# MCU.net
KiCad netlist of a schematic drawn in Altium Designer
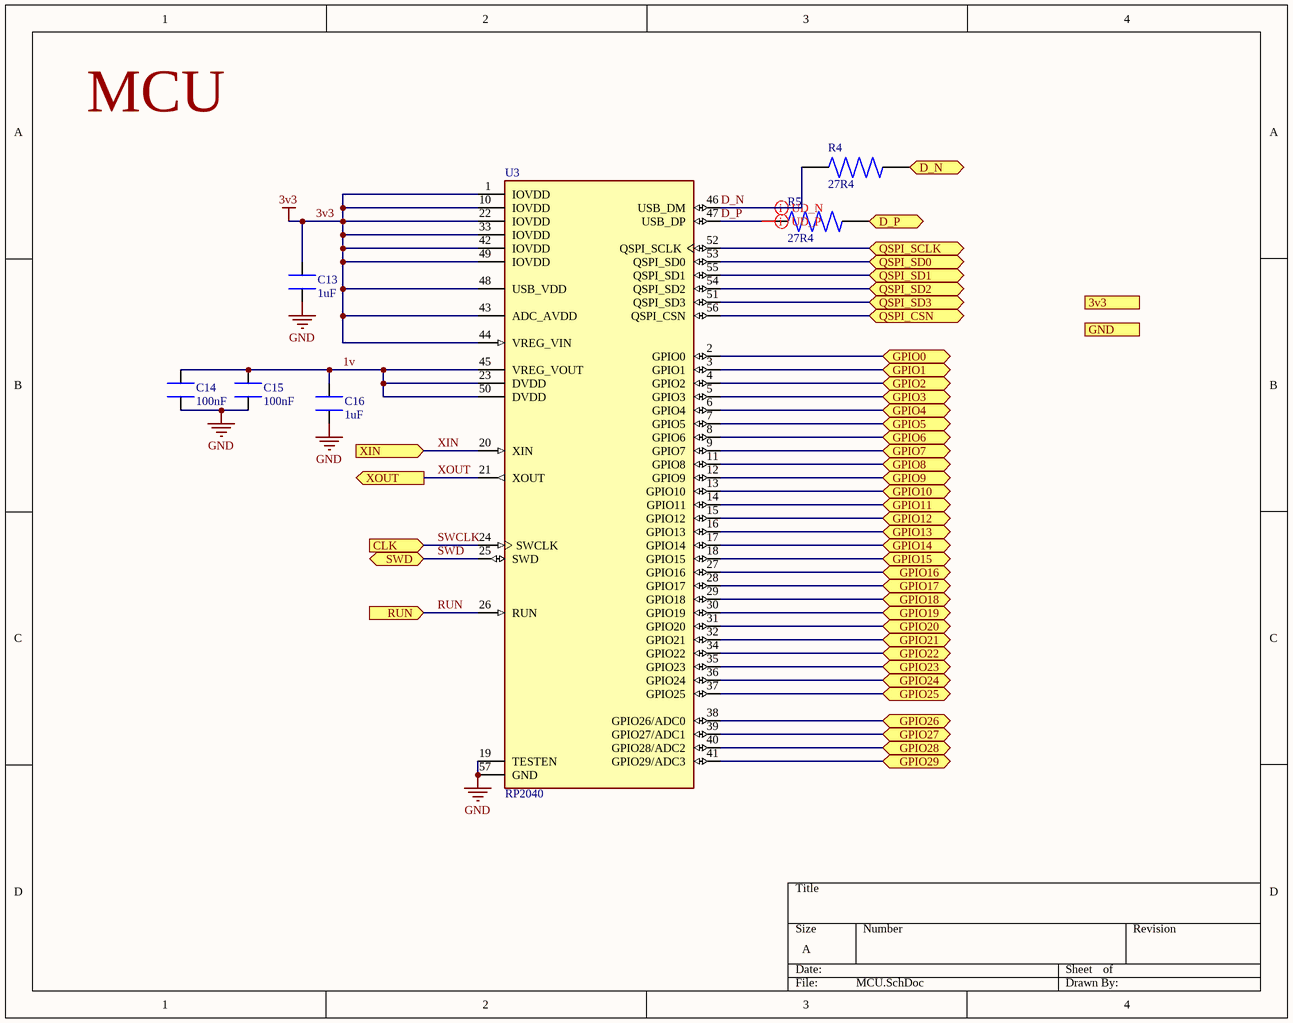
[diagram p0: MCU.SchDoc]

(export (version "E")
  (design (tool "Eeschema 10.0.6"))
  (components
    (comp (ref "C13")
      (value "1uF")
      (footprint "CC0603KRX5R8BB105")
      (description "SMD ceramic capasitor 1uF")
      (fields (field (name "MF") "Yageo") (field (name "MP") "CC0603KRX5R8BB105"))
      (libsource (lib "RP2040intLib") (part "CC0603KRX5R8BB105"))
    )
    (comp (ref "C14")
      (value "100nF")
      (footprint "CL10B104KB8NNNC")
      (description "SMD ceramic capacitor 0.1µF, tolerance ±10% 50V 0603 _1608 Metric_")
      (fields (field (name "MP") "CL10B104KB8NNNC") (field (name "MF") "Samsung Electro-Mechanics"))
      (libsource (lib "RP2040intLib") (part "CL10B104KB8NNNC"))
    )
    (comp (ref "C15")
      (value "100nF")
      (footprint "CL10B104KB8NNNC")
      (description "SMD ceramic capacitor 0.1µF, tolerance ±10% 50V 0603 _1608 Metric_")
      (fields (field (name "MP") "CL10B104KB8NNNC") (field (name "MF") "Samsung Electro-Mechanics"))
      (libsource (lib "RP2040intLib") (part "CL10B104KB8NNNC"))
    )
    (comp (ref "C16")
      (value "1uF")
      (footprint "CC0603KRX5R8BB105")
      (description "SMD ceramic capasitor 1uF")
      (fields (field (name "MF") "Yageo") (field (name "MP") "CC0603KRX5R8BB105"))
      (libsource (lib "RP2040intLib") (part "CC0603KRX5R8BB105"))
    )
    (comp (ref "R4")
      (value "27R4")
      (footprint "RC0603FR-0727R4L")
      (description "RES SMD 27.4 OHM 1% 1/10W 0603")
      (fields (field (name "MP") "RC0603FR-0727R4L"))
      (libsource (lib "RP2040intLib") (part "RC0603FR-0727R4L"))
    )
    (comp (ref "R5")
      (value "27R4")
      (footprint "RC0603FR-0727R4L")
      (description "RES SMD 27.4 OHM 1% 1/10W 0603")
      (fields (field (name "MP") "RC0603FR-0727R4L"))
      (libsource (lib "RP2040intLib") (part "RC0603FR-0727R4L"))
    )
    (comp (ref "U3")
      (value "RP2040")
      (footprint "RP2040")
      (description "RP2040 chip for Raspberry Pi Pico - ARM® Cortex®-M0+ MCU 32-Bit")
      (fields (field (name "MF") "Raspberry Pi"))
      (libsource (lib "RP2040intLib") (part "RP2040"))
    )
  )
  (nets
    (net (code "1") (name "/1v") (class "Default")
      (node (ref "C14") (pin "2") (pinfunction "2_2") (pintype "passive"))
      (node (ref "C15") (pin "2") (pinfunction "2_2") (pintype "passive"))
      (node (ref "C16") (pin "1") (pinfunction "1_1") (pintype "passive"))
      (node (ref "U3") (pin "23") (pinfunction "DVDD_23") (pintype "power_in"))
      (node (ref "U3") (pin "45") (pinfunction "VREG_VOUT_45") (pintype "power_in"))
      (node (ref "U3") (pin "50") (pinfunction "DVDD_50") (pintype "power_in"))
    )
    (net (code "2") (name "/D_N") (class "Default")
      (node (ref "R4") (pin "1") (pinfunction "1_1") (pintype "passive"))
      (node (ref "U3") (pin "46") (pinfunction "USB_DM_46") (pintype "bidirectional"))
    )
    (net (code "3") (name "/D_P") (class "Default")
      (node (ref "R5") (pin "1") (pinfunction "1_1") (pintype "passive"))
      (node (ref "U3") (pin "47") (pinfunction "USB_DP_47") (pintype "bidirectional"))
    )
    (net (code "4") (name "/GPIO0") (class "Default")
      (node (ref "U3") (pin "2") (pinfunction "GPIO0_2") (pintype "bidirectional"))
    )
    (net (code "5") (name "/GPIO1") (class "Default")
      (node (ref "U3") (pin "3") (pinfunction "GPIO1_3") (pintype "bidirectional"))
    )
    (net (code "6") (name "/GPIO2") (class "Default")
      (node (ref "U3") (pin "4") (pinfunction "GPIO2_4") (pintype "bidirectional"))
    )
    (net (code "7") (name "/GPIO3") (class "Default")
      (node (ref "U3") (pin "5") (pinfunction "GPIO3_5") (pintype "bidirectional"))
    )
    (net (code "8") (name "/GPIO4") (class "Default")
      (node (ref "U3") (pin "6") (pinfunction "GPIO4_6") (pintype "bidirectional"))
    )
    (net (code "9") (name "/GPIO5") (class "Default")
      (node (ref "U3") (pin "7") (pinfunction "GPIO5_7") (pintype "bidirectional"))
    )
    (net (code "10") (name "/GPIO6") (class "Default")
      (node (ref "U3") (pin "8") (pinfunction "GPIO6_8") (pintype "bidirectional"))
    )
    (net (code "11") (name "/GPIO7") (class "Default")
      (node (ref "U3") (pin "9") (pinfunction "GPIO7_9") (pintype "bidirectional"))
    )
    (net (code "12") (name "/GPIO8") (class "Default")
      (node (ref "U3") (pin "11") (pinfunction "GPIO8_11") (pintype "bidirectional"))
    )
    (net (code "13") (name "/GPIO9") (class "Default")
      (node (ref "U3") (pin "12") (pinfunction "GPIO9_12") (pintype "bidirectional"))
    )
    (net (code "14") (name "/GPIO10") (class "Default")
      (node (ref "U3") (pin "13") (pinfunction "GPIO10_13") (pintype "bidirectional"))
    )
    (net (code "15") (name "/GPIO11") (class "Default")
      (node (ref "U3") (pin "14") (pinfunction "GPIO11_14") (pintype "bidirectional"))
    )
    (net (code "16") (name "/GPIO12") (class "Default")
      (node (ref "U3") (pin "15") (pinfunction "GPIO12_15") (pintype "bidirectional"))
    )
    (net (code "17") (name "/GPIO13") (class "Default")
      (node (ref "U3") (pin "16") (pinfunction "GPIO13_16") (pintype "bidirectional"))
    )
    (net (code "18") (name "/GPIO14") (class "Default")
      (node (ref "U3") (pin "17") (pinfunction "GPIO14_17") (pintype "bidirectional"))
    )
    (net (code "19") (name "/GPIO15") (class "Default")
      (node (ref "U3") (pin "18") (pinfunction "GPIO15_18") (pintype "bidirectional"))
    )
    (net (code "20") (name "/GPIO16") (class "Default")
      (node (ref "U3") (pin "27") (pinfunction "GPIO16_27") (pintype "bidirectional"))
    )
    (net (code "21") (name "/GPIO17") (class "Default")
      (node (ref "U3") (pin "28") (pinfunction "GPIO17_28") (pintype "bidirectional"))
    )
    (net (code "22") (name "/GPIO18") (class "Default")
      (node (ref "U3") (pin "29") (pinfunction "GPIO18_29") (pintype "bidirectional"))
    )
    (net (code "23") (name "/GPIO19") (class "Default")
      (node (ref "U3") (pin "30") (pinfunction "GPIO19_30") (pintype "bidirectional"))
    )
    (net (code "24") (name "/GPIO20") (class "Default")
      (node (ref "U3") (pin "31") (pinfunction "GPIO20_31") (pintype "bidirectional"))
    )
    (net (code "25") (name "/GPIO21") (class "Default")
      (node (ref "U3") (pin "32") (pinfunction "GPIO21_32") (pintype "bidirectional"))
    )
    (net (code "26") (name "/GPIO22") (class "Default")
      (node (ref "U3") (pin "34") (pinfunction "GPIO22_34") (pintype "bidirectional"))
    )
    (net (code "27") (name "/GPIO23") (class "Default")
      (node (ref "U3") (pin "35") (pinfunction "GPIO23_35") (pintype "bidirectional"))
    )
    (net (code "28") (name "/GPIO24") (class "Default")
      (node (ref "U3") (pin "36") (pinfunction "GPIO24_36") (pintype "bidirectional"))
    )
    (net (code "29") (name "/GPIO25") (class "Default")
      (node (ref "U3") (pin "37") (pinfunction "GPIO25_37") (pintype "bidirectional"))
    )
    (net (code "30") (name "/GPIO26") (class "Default")
      (node (ref "U3") (pin "38") (pinfunction "GPIO26/ADC0_38") (pintype "bidirectional"))
    )
    (net (code "31") (name "/GPIO27") (class "Default")
      (node (ref "U3") (pin "39") (pinfunction "GPIO27/ADC1_39") (pintype "bidirectional"))
    )
    (net (code "32") (name "/GPIO28") (class "Default")
      (node (ref "U3") (pin "40") (pinfunction "GPIO28/ADC2_40") (pintype "bidirectional"))
    )
    (net (code "33") (name "/GPIO29") (class "Default")
      (node (ref "U3") (pin "41") (pinfunction "GPIO29/ADC3_41") (pintype "bidirectional"))
    )
    (net (code "34") (name "/QSPI_CSN") (class "Default")
      (node (ref "U3") (pin "56") (pinfunction "QSPI_CSN_56") (pintype "bidirectional"))
    )
    (net (code "35") (name "/QSPI_SCLK") (class "Default")
      (node (ref "U3") (pin "52") (pinfunction "QSPI_SCLK_52") (pintype "bidirectional"))
    )
    (net (code "36") (name "/QSPI_SD0") (class "Default")
      (node (ref "U3") (pin "53") (pinfunction "QSPI_SD0_53") (pintype "bidirectional"))
    )
    (net (code "37") (name "/QSPI_SD1") (class "Default")
      (node (ref "U3") (pin "55") (pinfunction "QSPI_SD1_55") (pintype "bidirectional"))
    )
    (net (code "38") (name "/QSPI_SD2") (class "Default")
      (node (ref "U3") (pin "54") (pinfunction "QSPI_SD2_54") (pintype "bidirectional"))
    )
    (net (code "39") (name "/QSPI_SD3") (class "Default")
      (node (ref "U3") (pin "51") (pinfunction "QSPI_SD3_51") (pintype "bidirectional"))
    )
    (net (code "40") (name "/RUN") (class "Default")
      (node (ref "U3") (pin "26") (pinfunction "RUN_26") (pintype "input"))
    )
    (net (code "41") (name "/SWCLK") (class "Default")
      (node (ref "U3") (pin "24") (pinfunction "SWCLK_24") (pintype "input"))
    )
    (net (code "42") (name "/SWD") (class "Default")
      (node (ref "U3") (pin "25") (pinfunction "SWD_25") (pintype "bidirectional"))
    )
    (net (code "43") (name "/XIN") (class "Default")
      (node (ref "U3") (pin "20") (pinfunction "XIN_20") (pintype "input"))
    )
    (net (code "44") (name "/XOUT") (class "Default")
      (node (ref "U3") (pin "21") (pinfunction "XOUT_21") (pintype "output"))
    )
    (net (code "45") (name "3v3") (class "Default")
      (node (ref "C13") (pin "1") (pinfunction "1_1") (pintype "passive"))
      (node (ref "U3") (pin "1") (pinfunction "IOVDD_1") (pintype "power_in"))
      (node (ref "U3") (pin "10") (pinfunction "IOVDD_10") (pintype "power_in"))
      (node (ref "U3") (pin "22") (pinfunction "IOVDD_22") (pintype "power_in"))
      (node (ref "U3") (pin "33") (pinfunction "IOVDD_33") (pintype "power_in"))
      (node (ref "U3") (pin "42") (pinfunction "IOVDD_42") (pintype "power_in"))
      (node (ref "U3") (pin "43") (pinfunction "ADC_AVDD_43") (pintype "power_in"))
      (node (ref "U3") (pin "44") (pinfunction "VREG_VIN_44") (pintype "input"))
      (node (ref "U3") (pin "48") (pinfunction "USB_VDD_48") (pintype "power_in"))
      (node (ref "U3") (pin "49") (pinfunction "IOVDD_49") (pintype "power_in"))
    )
    (net (code "46") (name "GND") (class "Default")
      (node (ref "C13") (pin "2") (pinfunction "2_2") (pintype "passive"))
      (node (ref "C14") (pin "1") (pinfunction "1_1") (pintype "passive"))
      (node (ref "C15") (pin "1") (pinfunction "1_1") (pintype "passive"))
      (node (ref "C16") (pin "2") (pinfunction "2_2") (pintype "passive"))
      (node (ref "U3") (pin "19") (pinfunction "TESTEN_19") (pintype "passive"))
      (node (ref "U3") (pin "57") (pinfunction "GND_57") (pintype "power_in"))
    )
    (net (code "47") (name "unconnected-(R4-Pad2)") (class "Default")
      (node (ref "R4") (pin "2") (pinfunction "2_2") (pintype "passive"))
    )
    (net (code "48") (name "unconnected-(R5-Pad2)") (class "Default")
      (node (ref "R5") (pin "2") (pinfunction "2_2") (pintype "passive"))
    )
  )
)
